# MainBoard.net
KiCad netlist of a schematic drawn in EAGLE
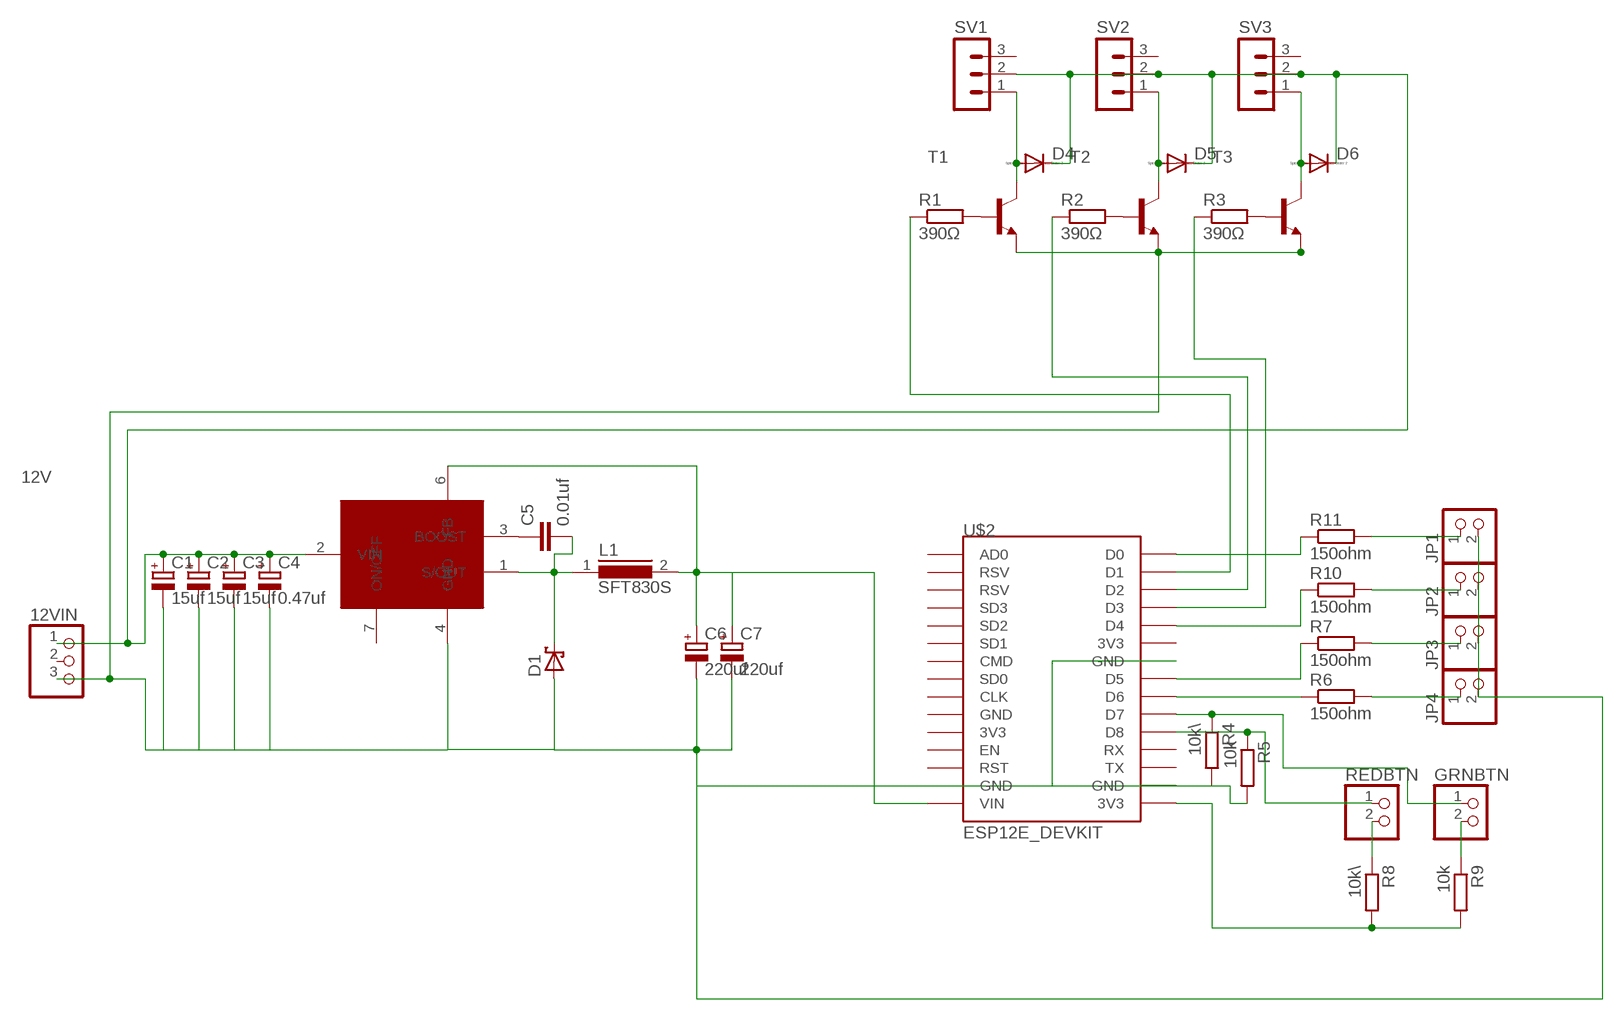
[diagram p0: schematic, sheet 1]

(export (version "E")
  (design (tool "Eeschema 10.0.6"))
  (components
    (comp (ref "12VIN")
      (value "PINHD-1X3")
      (footprint "eagle-import:1X03")
      (libsource (lib "eagle-import") (part "PINHD-1X3"))
    )
    (comp (ref "C1")
      (value "15uf")
      (footprint "eagle-import:E2,5-6E")
      (libsource (lib "eagle-import") (part "CPOL-EUE2,5-6E"))
    )
    (comp (ref "C2")
      (value "15uf")
      (footprint "eagle-import:E2,5-6E")
      (libsource (lib "eagle-import") (part "CPOL-EUE2,5-6E"))
    )
    (comp (ref "C3")
      (value "15uf")
      (footprint "eagle-import:E2,5-6E")
      (libsource (lib "eagle-import") (part "CPOL-EUE2,5-6E"))
    )
    (comp (ref "C4")
      (value "0.47uf")
      (footprint "eagle-import:E2,5-6E")
      (libsource (lib "eagle-import") (part "CPOL-EUE2,5-6E"))
    )
    (comp (ref "C5")
      (value "0.01uf")
      (footprint "eagle-import:C050-024X044")
      (libsource (lib "eagle-import") (part "C-EU050-024X044"))
    )
    (comp (ref "C6")
      (value "220uf")
      (footprint "eagle-import:E2,5-6E")
      (libsource (lib "eagle-import") (part "CPOL-EUE2,5-6E"))
    )
    (comp (ref "C7")
      (value "220uf")
      (footprint "eagle-import:E2,5-6E")
      (libsource (lib "eagle-import") (part "CPOL-EUE2,5-6E"))
    )
    (comp (ref "D1")
      (value "SCHOTTKY-DIODEC4111-15")
      (footprint "eagle-import:C4111-15")
      (libsource (lib "eagle-import") (part "SCHOTTKY-DIODEC4111-15"))
    )
    (comp (ref "D4")
      (value "DIODE-D-2.5")
      (footprint "eagle-import:D-2.5")
      (libsource (lib "eagle-import") (part "DIODE-D-2.5"))
    )
    (comp (ref "D5")
      (value "DIODE-D-2.5")
      (footprint "eagle-import:D-2.5")
      (libsource (lib "eagle-import") (part "DIODE-D-2.5"))
    )
    (comp (ref "D6")
      (value "DIODE-D-2.5")
      (footprint "eagle-import:D-2.5")
      (libsource (lib "eagle-import") (part "DIODE-D-2.5"))
    )
    (comp (ref "GRNBTN")
      (value "PINHD-1X2")
      (footprint "eagle-import:1X02")
      (libsource (lib "eagle-import") (part "PINHD-1X2"))
    )
    (comp (ref "JP1")
      (value "PINHD-1X2")
      (footprint "eagle-import:1X02")
      (libsource (lib "eagle-import") (part "PINHD-1X2"))
    )
    (comp (ref "JP2")
      (value "PINHD-1X2")
      (footprint "eagle-import:1X02")
      (libsource (lib "eagle-import") (part "PINHD-1X2"))
    )
    (comp (ref "JP3")
      (value "PINHD-1X2")
      (footprint "eagle-import:1X02")
      (libsource (lib "eagle-import") (part "PINHD-1X2"))
    )
    (comp (ref "JP4")
      (value "PINHD-1X2")
      (footprint "eagle-import:1X02")
      (libsource (lib "eagle-import") (part "PINHD-1X2"))
    )
    (comp (ref "L1")
      (value "SFT830S")
      (footprint "eagle-import:SFT830S")
      (libsource (lib "eagle-import") (part "SFT830S"))
    )
    (comp (ref "R1")
      (value "390Ω")
      (footprint "eagle-import:0207_5V")
      (libsource (lib "eagle-import") (part "resistor_R-EU_0207/5V"))
    )
    (comp (ref "R2")
      (value "390Ω")
      (footprint "eagle-import:0207_5V")
      (libsource (lib "eagle-import") (part "resistor_R-EU_0207/5V"))
    )
    (comp (ref "R3")
      (value "390Ω")
      (footprint "eagle-import:0207_5V")
      (libsource (lib "eagle-import") (part "resistor_R-EU_0207/5V"))
    )
    (comp (ref "R4")
      (value "10k\\")
      (footprint "eagle-import:0207_5V")
      (libsource (lib "eagle-import") (part "resistor_R-EU_0207/5V"))
    )
    (comp (ref "R5")
      (value "10k")
      (footprint "eagle-import:0207_5V")
      (libsource (lib "eagle-import") (part "resistor_R-EU_0207/5V"))
    )
    (comp (ref "R6")
      (value "150ohm")
      (footprint "eagle-import:0204V")
      (libsource (lib "eagle-import") (part "R-EU_0204/2V"))
    )
    (comp (ref "R7")
      (value "150ohm")
      (footprint "eagle-import:0204V")
      (libsource (lib "eagle-import") (part "R-EU_0204/2V"))
    )
    (comp (ref "R8")
      (value "10k\\")
      (footprint "eagle-import:0207_5V")
      (libsource (lib "eagle-import") (part "resistor_R-EU_0207/5V"))
    )
    (comp (ref "R9")
      (value "10k")
      (footprint "eagle-import:0207_5V")
      (libsource (lib "eagle-import") (part "resistor_R-EU_0207/5V"))
    )
    (comp (ref "R10")
      (value "150ohm")
      (footprint "eagle-import:0204V")
      (libsource (lib "eagle-import") (part "R-EU_0204/2V"))
    )
    (comp (ref "R11")
      (value "150ohm")
      (footprint "eagle-import:0204V")
      (libsource (lib "eagle-import") (part "R-EU_0204/2V"))
    )
    (comp (ref "REDBTN")
      (value "PINHD-1X2")
      (footprint "eagle-import:1X02")
      (libsource (lib "eagle-import") (part "PINHD-1X2"))
    )
    (comp (ref "SV1")
      (value "MA03-1")
      (footprint "eagle-import:MA03-1")
      (libsource (lib "eagle-import") (part "MA03-1"))
    )
    (comp (ref "SV2")
      (value "MA03-1")
      (footprint "eagle-import:MA03-1")
      (libsource (lib "eagle-import") (part "MA03-1"))
    )
    (comp (ref "SV3")
      (value "MA03-1")
      (footprint "eagle-import:MA03-1")
      (libsource (lib "eagle-import") (part "MA03-1"))
    )
    (comp (ref "T1")
      (value "-NPN-TO92")
      (footprint "eagle-import:TO92")
      (libsource (lib "eagle-import") (part "-NPN-TO92"))
    )
    (comp (ref "T2")
      (value "-NPN-TO92")
      (footprint "eagle-import:TO92")
      (libsource (lib "eagle-import") (part "-NPN-TO92"))
    )
    (comp (ref "T3")
      (value "-NPN-TO92")
      (footprint "eagle-import:TO92")
      (libsource (lib "eagle-import") (part "-NPN-TO92"))
    )
    (comp (ref "U$1")
      (value "LM2678T-5")
      (footprint "eagle-import:TO-220")
      (libsource (lib "eagle-import") (part "LM2678T-5"))
    )
    (comp (ref "U$2")
      (value "ESP12E_DEVKIT")
      (footprint "eagle-import:ESP12E_DEVKIT")
      (libsource (lib "eagle-import") (part "ESP12E_DEVKIT"))
    )
  )
  (nets
    (net (code "1") (name "/12V") (class "Default")
      (node (ref "12VIN") (pin "1") (pinfunction "1_1") (pintype "passive"))
      (node (ref "C1") (pin "+") (pinfunction "+_+") (pintype "passive"))
      (node (ref "C2") (pin "+") (pinfunction "+_+") (pintype "passive"))
      (node (ref "C3") (pin "+") (pinfunction "+_+") (pintype "passive"))
      (node (ref "C4") (pin "+") (pinfunction "+_+") (pintype "passive"))
      (node (ref "D4") (pin "C") (pinfunction "C_C") (pintype "passive"))
      (node (ref "D5") (pin "C") (pinfunction "C_C") (pintype "passive"))
      (node (ref "D6") (pin "C") (pinfunction "C_C") (pintype "passive"))
      (node (ref "SV1") (pin "2") (pinfunction "2_2") (pintype "passive"))
      (node (ref "SV2") (pin "2") (pinfunction "2_2") (pintype "passive"))
      (node (ref "SV3") (pin "2") (pinfunction "2_2") (pintype "passive"))
      (node (ref "U$1") (pin "2") (pinfunction "VIN_2") (pintype "bidirectional"))
    )
    (net (code "2") (name "Net-(GRNBTN-Pad1)") (class "Default")
      (node (ref "GRNBTN") (pin "1") (pinfunction "1_1") (pintype "passive"))
      (node (ref "R4") (pin "1") (pinfunction "1_1") (pintype "passive"))
      (node (ref "U$2") (pin "D7") (pinfunction "D7_D7") (pintype "bidirectional"))
    )
    (net (code "3") (name "Net-(GRNBTN-Pad2)") (class "Default")
      (node (ref "GRNBTN") (pin "2") (pinfunction "2_2") (pintype "passive"))
      (node (ref "R9") (pin "1") (pinfunction "1_1") (pintype "passive"))
    )
    (net (code "4") (name "Net-(JP1-Pad1)") (class "Default")
      (node (ref "JP1") (pin "1") (pinfunction "1_1") (pintype "passive"))
      (node (ref "R11") (pin "2") (pinfunction "2_2") (pintype "passive"))
    )
    (net (code "5") (name "Net-(JP2-Pad1)") (class "Default")
      (node (ref "JP2") (pin "1") (pinfunction "1_1") (pintype "passive"))
      (node (ref "R10") (pin "2") (pinfunction "2_2") (pintype "passive"))
    )
    (net (code "6") (name "Net-(JP3-Pad1)") (class "Default")
      (node (ref "JP3") (pin "1") (pinfunction "1_1") (pintype "passive"))
      (node (ref "R7") (pin "2") (pinfunction "2_2") (pintype "passive"))
    )
    (net (code "7") (name "Net-(JP4-Pad1)") (class "Default")
      (node (ref "JP4") (pin "1") (pinfunction "1_1") (pintype "passive"))
      (node (ref "R6") (pin "2") (pinfunction "2_2") (pintype "passive"))
    )
    (net (code "8") (name "Net-(R1-Pad1)") (class "Default")
      (node (ref "R1") (pin "1") (pinfunction "1_1") (pintype "passive"))
      (node (ref "U$2") (pin "D1") (pinfunction "D1_D1") (pintype "bidirectional"))
    )
    (net (code "9") (name "Net-(R2-Pad1)") (class "Default")
      (node (ref "R2") (pin "1") (pinfunction "1_1") (pintype "passive"))
      (node (ref "U$2") (pin "D2") (pinfunction "D2_D2") (pintype "bidirectional"))
    )
    (net (code "10") (name "Net-(R3-Pad1)") (class "Default")
      (node (ref "R3") (pin "1") (pinfunction "1_1") (pintype "passive"))
      (node (ref "U$2") (pin "D3") (pinfunction "D3_D3") (pintype "bidirectional"))
    )
    (net (code "11") (name "Net-(R5-Pad1)") (class "Default")
      (node (ref "R5") (pin "1") (pinfunction "1_1") (pintype "passive"))
      (node (ref "REDBTN") (pin "1") (pinfunction "1_1") (pintype "passive"))
      (node (ref "U$2") (pin "D8") (pinfunction "D8_D8") (pintype "bidirectional"))
    )
    (net (code "12") (name "Net-(R6-Pad1)") (class "Default")
      (node (ref "R6") (pin "1") (pinfunction "1_1") (pintype "passive"))
      (node (ref "U$2") (pin "D6") (pinfunction "D6_D6") (pintype "bidirectional"))
    )
    (net (code "13") (name "Net-(R7-Pad1)") (class "Default")
      (node (ref "R7") (pin "1") (pinfunction "1_1") (pintype "passive"))
      (node (ref "U$2") (pin "D5") (pinfunction "D5_D5") (pintype "bidirectional"))
    )
    (net (code "14") (name "Net-(R8-Pad1)") (class "Default")
      (node (ref "R8") (pin "1") (pinfunction "1_1") (pintype "passive"))
      (node (ref "REDBTN") (pin "2") (pinfunction "2_2") (pintype "passive"))
    )
    (net (code "15") (name "Net-(R8-Pad2)") (class "Default")
      (node (ref "R8") (pin "2") (pinfunction "2_2") (pintype "passive"))
      (node (ref "R9") (pin "2") (pinfunction "2_2") (pintype "passive"))
      (node (ref "U$2") (pin "3V3@2") (pinfunction "3V3_3V3@2") (pintype "bidirectional"))
    )
    (net (code "16") (name "Net-(R10-Pad1)") (class "Default")
      (node (ref "R10") (pin "1") (pinfunction "1_1") (pintype "passive"))
      (node (ref "U$2") (pin "D4") (pinfunction "D4_D4") (pintype "bidirectional"))
    )
    (net (code "17") (name "Net-(R11-Pad1)") (class "Default")
      (node (ref "R11") (pin "1") (pinfunction "1_1") (pintype "passive"))
      (node (ref "U$2") (pin "D0") (pinfunction "D0_D0") (pintype "bidirectional"))
    )
    (net (code "18") (name "Net-(T1-B)") (class "Default")
      (node (ref "R1") (pin "2") (pinfunction "2_2") (pintype "passive"))
      (node (ref "T1") (pin "2") (pinfunction "B_2") (pintype "passive"))
    )
    (net (code "19") (name "Net-(T1-C)") (class "Default")
      (node (ref "D4") (pin "A") (pinfunction "A_A") (pintype "passive"))
      (node (ref "SV1") (pin "1") (pinfunction "1_1") (pintype "passive"))
      (node (ref "T1") (pin "3") (pinfunction "C_3") (pintype "passive"))
    )
    (net (code "20") (name "Net-(T1-E)") (class "Default")
      (node (ref "12VIN") (pin "3") (pinfunction "3_3") (pintype "passive"))
      (node (ref "C1") (pin "-") (pinfunction "-_-") (pintype "passive"))
      (node (ref "C2") (pin "-") (pinfunction "-_-") (pintype "passive"))
      (node (ref "C3") (pin "-") (pinfunction "-_-") (pintype "passive"))
      (node (ref "C4") (pin "-") (pinfunction "-_-") (pintype "passive"))
      (node (ref "C6") (pin "-") (pinfunction "-_-") (pintype "passive"))
      (node (ref "C7") (pin "-") (pinfunction "-_-") (pintype "passive"))
      (node (ref "D1") (pin "A") (pinfunction "A_A") (pintype "passive"))
      (node (ref "JP1") (pin "2") (pinfunction "2_2") (pintype "passive"))
      (node (ref "JP2") (pin "2") (pinfunction "2_2") (pintype "passive"))
      (node (ref "JP3") (pin "2") (pinfunction "2_2") (pintype "passive"))
      (node (ref "JP4") (pin "2") (pinfunction "2_2") (pintype "passive"))
      (node (ref "R4") (pin "2") (pinfunction "2_2") (pintype "passive"))
      (node (ref "R5") (pin "2") (pinfunction "2_2") (pintype "passive"))
      (node (ref "T1") (pin "1") (pinfunction "E_1") (pintype "passive"))
      (node (ref "T2") (pin "1") (pinfunction "E_1") (pintype "passive"))
      (node (ref "T3") (pin "1") (pinfunction "E_1") (pintype "passive"))
      (node (ref "U$1") (pin "4") (pinfunction "GND_4") (pintype "bidirectional"))
      (node (ref "U$2") (pin "GND@1") (pinfunction "GND_GND@1") (pintype "bidirectional"))
      (node (ref "U$2") (pin "GND@2") (pinfunction "GND_GND@2") (pintype "bidirectional"))
      (node (ref "U$2") (pin "GND@3") (pinfunction "GND_GND@3") (pintype "bidirectional"))
    )
    (net (code "21") (name "Net-(T2-B)") (class "Default")
      (node (ref "R2") (pin "2") (pinfunction "2_2") (pintype "passive"))
      (node (ref "T2") (pin "2") (pinfunction "B_2") (pintype "passive"))
    )
    (net (code "22") (name "Net-(T2-C)") (class "Default")
      (node (ref "D5") (pin "A") (pinfunction "A_A") (pintype "passive"))
      (node (ref "SV2") (pin "1") (pinfunction "1_1") (pintype "passive"))
      (node (ref "T2") (pin "3") (pinfunction "C_3") (pintype "passive"))
    )
    (net (code "23") (name "Net-(T3-B)") (class "Default")
      (node (ref "R3") (pin "2") (pinfunction "2_2") (pintype "passive"))
      (node (ref "T3") (pin "2") (pinfunction "B_2") (pintype "passive"))
    )
    (net (code "24") (name "Net-(T3-C)") (class "Default")
      (node (ref "D6") (pin "A") (pinfunction "A_A") (pintype "passive"))
      (node (ref "SV3") (pin "1") (pinfunction "1_1") (pintype "passive"))
      (node (ref "T3") (pin "3") (pinfunction "C_3") (pintype "passive"))
    )
    (net (code "25") (name "Net-(U$1-BOOST)") (class "Default")
      (node (ref "C5") (pin "1") (pinfunction "1_1") (pintype "passive"))
      (node (ref "U$1") (pin "3") (pinfunction "BOOST_3") (pintype "bidirectional"))
    )
    (net (code "26") (name "Net-(U$1-FB)") (class "Default")
      (node (ref "C6") (pin "+") (pinfunction "+_+") (pintype "passive"))
      (node (ref "C7") (pin "+") (pinfunction "+_+") (pintype "passive"))
      (node (ref "L1") (pin "2") (pinfunction "2_2") (pintype "passive"))
      (node (ref "U$1") (pin "6") (pinfunction "FB_6") (pintype "bidirectional"))
      (node (ref "U$2") (pin "VIN") (pinfunction "VIN_VIN") (pintype "bidirectional"))
    )
    (net (code "27") (name "Net-(U$1-S{slash}OUT)") (class "Default")
      (node (ref "C5") (pin "2") (pinfunction "2_2") (pintype "passive"))
      (node (ref "D1") (pin "C") (pinfunction "C_C") (pintype "passive"))
      (node (ref "L1") (pin "1") (pinfunction "1_1") (pintype "passive"))
      (node (ref "U$1") (pin "1") (pinfunction "S/OUT_1") (pintype "bidirectional"))
    )
    (net (code "28") (name "unconnected-(12VIN-Pad2)") (class "Default")
      (node (ref "12VIN") (pin "2") (pinfunction "2_2") (pintype "passive"))
    )
    (net (code "29") (name "unconnected-(SV1-Pad3)") (class "Default")
      (node (ref "SV1") (pin "3") (pinfunction "3_3") (pintype "passive"))
    )
    (net (code "30") (name "unconnected-(SV2-Pad3)") (class "Default")
      (node (ref "SV2") (pin "3") (pinfunction "3_3") (pintype "passive"))
    )
    (net (code "31") (name "unconnected-(SV3-Pad3)") (class "Default")
      (node (ref "SV3") (pin "3") (pinfunction "3_3") (pintype "passive"))
    )
    (net (code "32") (name "unconnected-(U$1-ON{slash}OFF-Pad7)") (class "Default")
      (node (ref "U$1") (pin "7") (pinfunction "ON/OFF_7") (pintype "bidirectional"))
    )
    (net (code "33") (name "unconnected-(U$2-3V3-Pad3V3@0)") (class "Default")
      (node (ref "U$2") (pin "3V3@0") (pinfunction "3V3_3V3@0") (pintype "bidirectional"))
    )
    (net (code "34") (name "unconnected-(U$2-3V3-Pad3V3@1)") (class "Default")
      (node (ref "U$2") (pin "3V3@1") (pinfunction "3V3_3V3@1") (pintype "bidirectional"))
    )
    (net (code "35") (name "unconnected-(U$2-GND-PadGND@0)") (class "Default")
      (node (ref "U$2") (pin "GND@0") (pinfunction "GND_GND@0") (pintype "bidirectional"))
    )
    (net (code "36") (name "unconnected-(U$2-PadAD0)") (class "Default")
      (node (ref "U$2") (pin "AD0") (pinfunction "AD0_AD0") (pintype "bidirectional"))
    )
    (net (code "37") (name "unconnected-(U$2-PadCLK)") (class "Default")
      (node (ref "U$2") (pin "CLK") (pinfunction "CLK_CLK") (pintype "bidirectional"))
    )
    (net (code "38") (name "unconnected-(U$2-PadCMD)") (class "Default")
      (node (ref "U$2") (pin "CMD") (pinfunction "CMD_CMD") (pintype "bidirectional"))
    )
    (net (code "39") (name "unconnected-(U$2-PadEN)") (class "Default")
      (node (ref "U$2") (pin "EN") (pinfunction "EN_EN") (pintype "bidirectional"))
    )
    (net (code "40") (name "unconnected-(U$2-PadRST)") (class "Default")
      (node (ref "U$2") (pin "RST") (pinfunction "RST_RST") (pintype "bidirectional"))
    )
    (net (code "41") (name "unconnected-(U$2-PadRX)") (class "Default")
      (node (ref "U$2") (pin "RX") (pinfunction "RX_RX") (pintype "bidirectional"))
    )
    (net (code "42") (name "unconnected-(U$2-PadSD0)") (class "Default")
      (node (ref "U$2") (pin "SD0") (pinfunction "SD0_SD0") (pintype "bidirectional"))
    )
    (net (code "43") (name "unconnected-(U$2-PadSD1)") (class "Default")
      (node (ref "U$2") (pin "SD1") (pinfunction "SD1_SD1") (pintype "bidirectional"))
    )
    (net (code "44") (name "unconnected-(U$2-PadSD2)") (class "Default")
      (node (ref "U$2") (pin "SD2") (pinfunction "SD2_SD2") (pintype "bidirectional"))
    )
    (net (code "45") (name "unconnected-(U$2-PadSD3)") (class "Default")
      (node (ref "U$2") (pin "SD3") (pinfunction "SD3_SD3") (pintype "bidirectional"))
    )
    (net (code "46") (name "unconnected-(U$2-PadTX)") (class "Default")
      (node (ref "U$2") (pin "TX") (pinfunction "TX_TX") (pintype "bidirectional"))
    )
    (net (code "47") (name "unconnected-(U$2-RSV-PadRSV@0)") (class "Default")
      (node (ref "U$2") (pin "RSV@0") (pinfunction "RSV_RSV@0") (pintype "bidirectional"))
    )
    (net (code "48") (name "unconnected-(U$2-RSV-PadRSV@1)") (class "Default")
      (node (ref "U$2") (pin "RSV@1") (pinfunction "RSV_RSV@1") (pintype "bidirectional"))
    )
  )
)
